# pressure_sensors.net
KiCad netlist of a schematic drawn in EAGLE
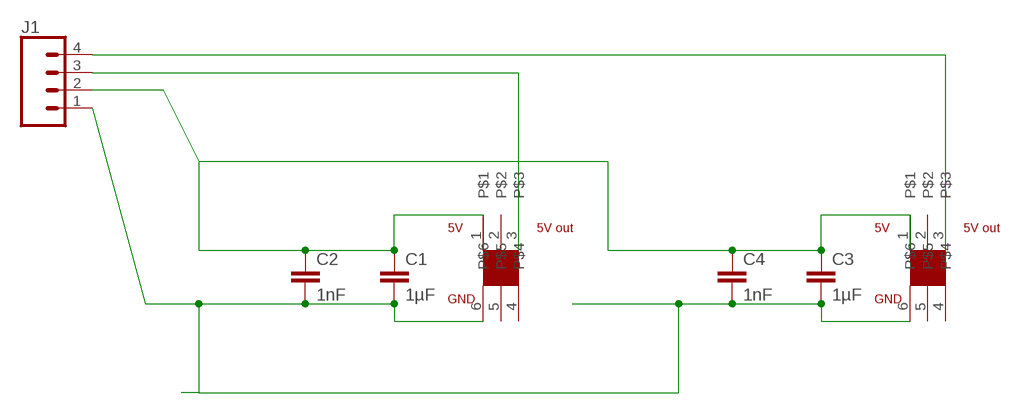
[diagram p0: schematic, sheet 1]

(export (version "E")
  (design (tool "Eeschema 10.0.6"))
  (components
    (comp (ref "C1")
      (value "1µF")
      (footprint "eagle-import:C050-030X075")
      (libsource (lib "eagle-import") (part "C-EU050-030X075"))
    )
    (comp (ref "C2")
      (value "1nF")
      (footprint "eagle-import:C050-030X075")
      (libsource (lib "eagle-import") (part "C-EU050-030X075"))
    )
    (comp (ref "C3")
      (value "1µF")
      (footprint "eagle-import:C050-030X075")
      (libsource (lib "eagle-import") (part "C-EU050-030X075"))
    )
    (comp (ref "C4")
      (value "1nF")
      (footprint "eagle-import:C050-030X075")
      (libsource (lib "eagle-import") (part "C-EU050-030X075"))
    )
    (comp (ref "J1")
      (value "CONN_04")
      (footprint "eagle-import:1X04")
      (libsource (lib "eagle-import") (part "CONN_04"))
    )
    (comp (ref "U$1")
      (value "1")
      (footprint "eagle-import:DIP750W53P254L720H850Q6B")
      (libsource (lib "eagle-import") (part "ADP5101"))
    )
    (comp (ref "U$2")
      (value "ADP5101")
      (footprint "eagle-import:DIP750W53P254L720H850Q6B")
      (libsource (lib "eagle-import") (part "ADP5101"))
    )
  )
  (nets
    (net (code "1") (name "Net-(U$1-P$1)") (class "Default")
      (node (ref "C1") (pin "1") (pinfunction "1_1") (pintype "passive"))
      (node (ref "C2") (pin "1") (pinfunction "1_1") (pintype "passive"))
      (node (ref "C3") (pin "1") (pinfunction "1_1") (pintype "passive"))
      (node (ref "C4") (pin "1") (pinfunction "1_1") (pintype "passive"))
      (node (ref "J1") (pin "2") (pinfunction "2_2") (pintype "passive"))
      (node (ref "U$1") (pin "1") (pinfunction "P$1_1") (pintype "power_in"))
      (node (ref "U$2") (pin "1") (pinfunction "P$1_1") (pintype "power_in"))
    )
    (net (code "2") (name "Net-(U$1-P$3)") (class "Default")
      (node (ref "J1") (pin "3") (pinfunction "3_3") (pintype "passive"))
      (node (ref "U$1") (pin "3") (pinfunction "P$3_3") (pintype "output"))
    )
    (net (code "3") (name "Net-(U$1-P$6)") (class "Default")
      (node (ref "C1") (pin "2") (pinfunction "2_2") (pintype "passive"))
      (node (ref "C2") (pin "2") (pinfunction "2_2") (pintype "passive"))
      (node (ref "C3") (pin "2") (pinfunction "2_2") (pintype "passive"))
      (node (ref "C4") (pin "2") (pinfunction "2_2") (pintype "passive"))
      (node (ref "J1") (pin "1") (pinfunction "1_1") (pintype "passive"))
      (node (ref "U$1") (pin "6") (pinfunction "P$6_6") (pintype "power_in"))
      (node (ref "U$2") (pin "6") (pinfunction "P$6_6") (pintype "power_in"))
    )
    (net (code "4") (name "Net-(U$2-P$3)") (class "Default")
      (node (ref "J1") (pin "4") (pinfunction "4_4") (pintype "passive"))
      (node (ref "U$2") (pin "3") (pinfunction "P$3_3") (pintype "output"))
    )
    (net (code "5") (name "unconnected-(U$1-P$2-Pad2)") (class "Default")
      (node (ref "U$1") (pin "2") (pinfunction "P$2_2") (pintype "no_connect"))
    )
    (net (code "6") (name "unconnected-(U$1-P$4-Pad4)") (class "Default")
      (node (ref "U$1") (pin "4") (pinfunction "P$4_4") (pintype "no_connect"))
    )
    (net (code "7") (name "unconnected-(U$1-P$5-Pad5)") (class "Default")
      (node (ref "U$1") (pin "5") (pinfunction "P$5_5") (pintype "no_connect"))
    )
    (net (code "8") (name "unconnected-(U$2-P$2-Pad2)") (class "Default")
      (node (ref "U$2") (pin "2") (pinfunction "P$2_2") (pintype "no_connect"))
    )
    (net (code "9") (name "unconnected-(U$2-P$4-Pad4)") (class "Default")
      (node (ref "U$2") (pin "4") (pinfunction "P$4_4") (pintype "no_connect"))
    )
    (net (code "10") (name "unconnected-(U$2-P$5-Pad5)") (class "Default")
      (node (ref "U$2") (pin "5") (pinfunction "P$5_5") (pintype "no_connect"))
    )
  )
)
